# 1_Interface.net
KiCad netlist of a schematic drawn in Altium Designer
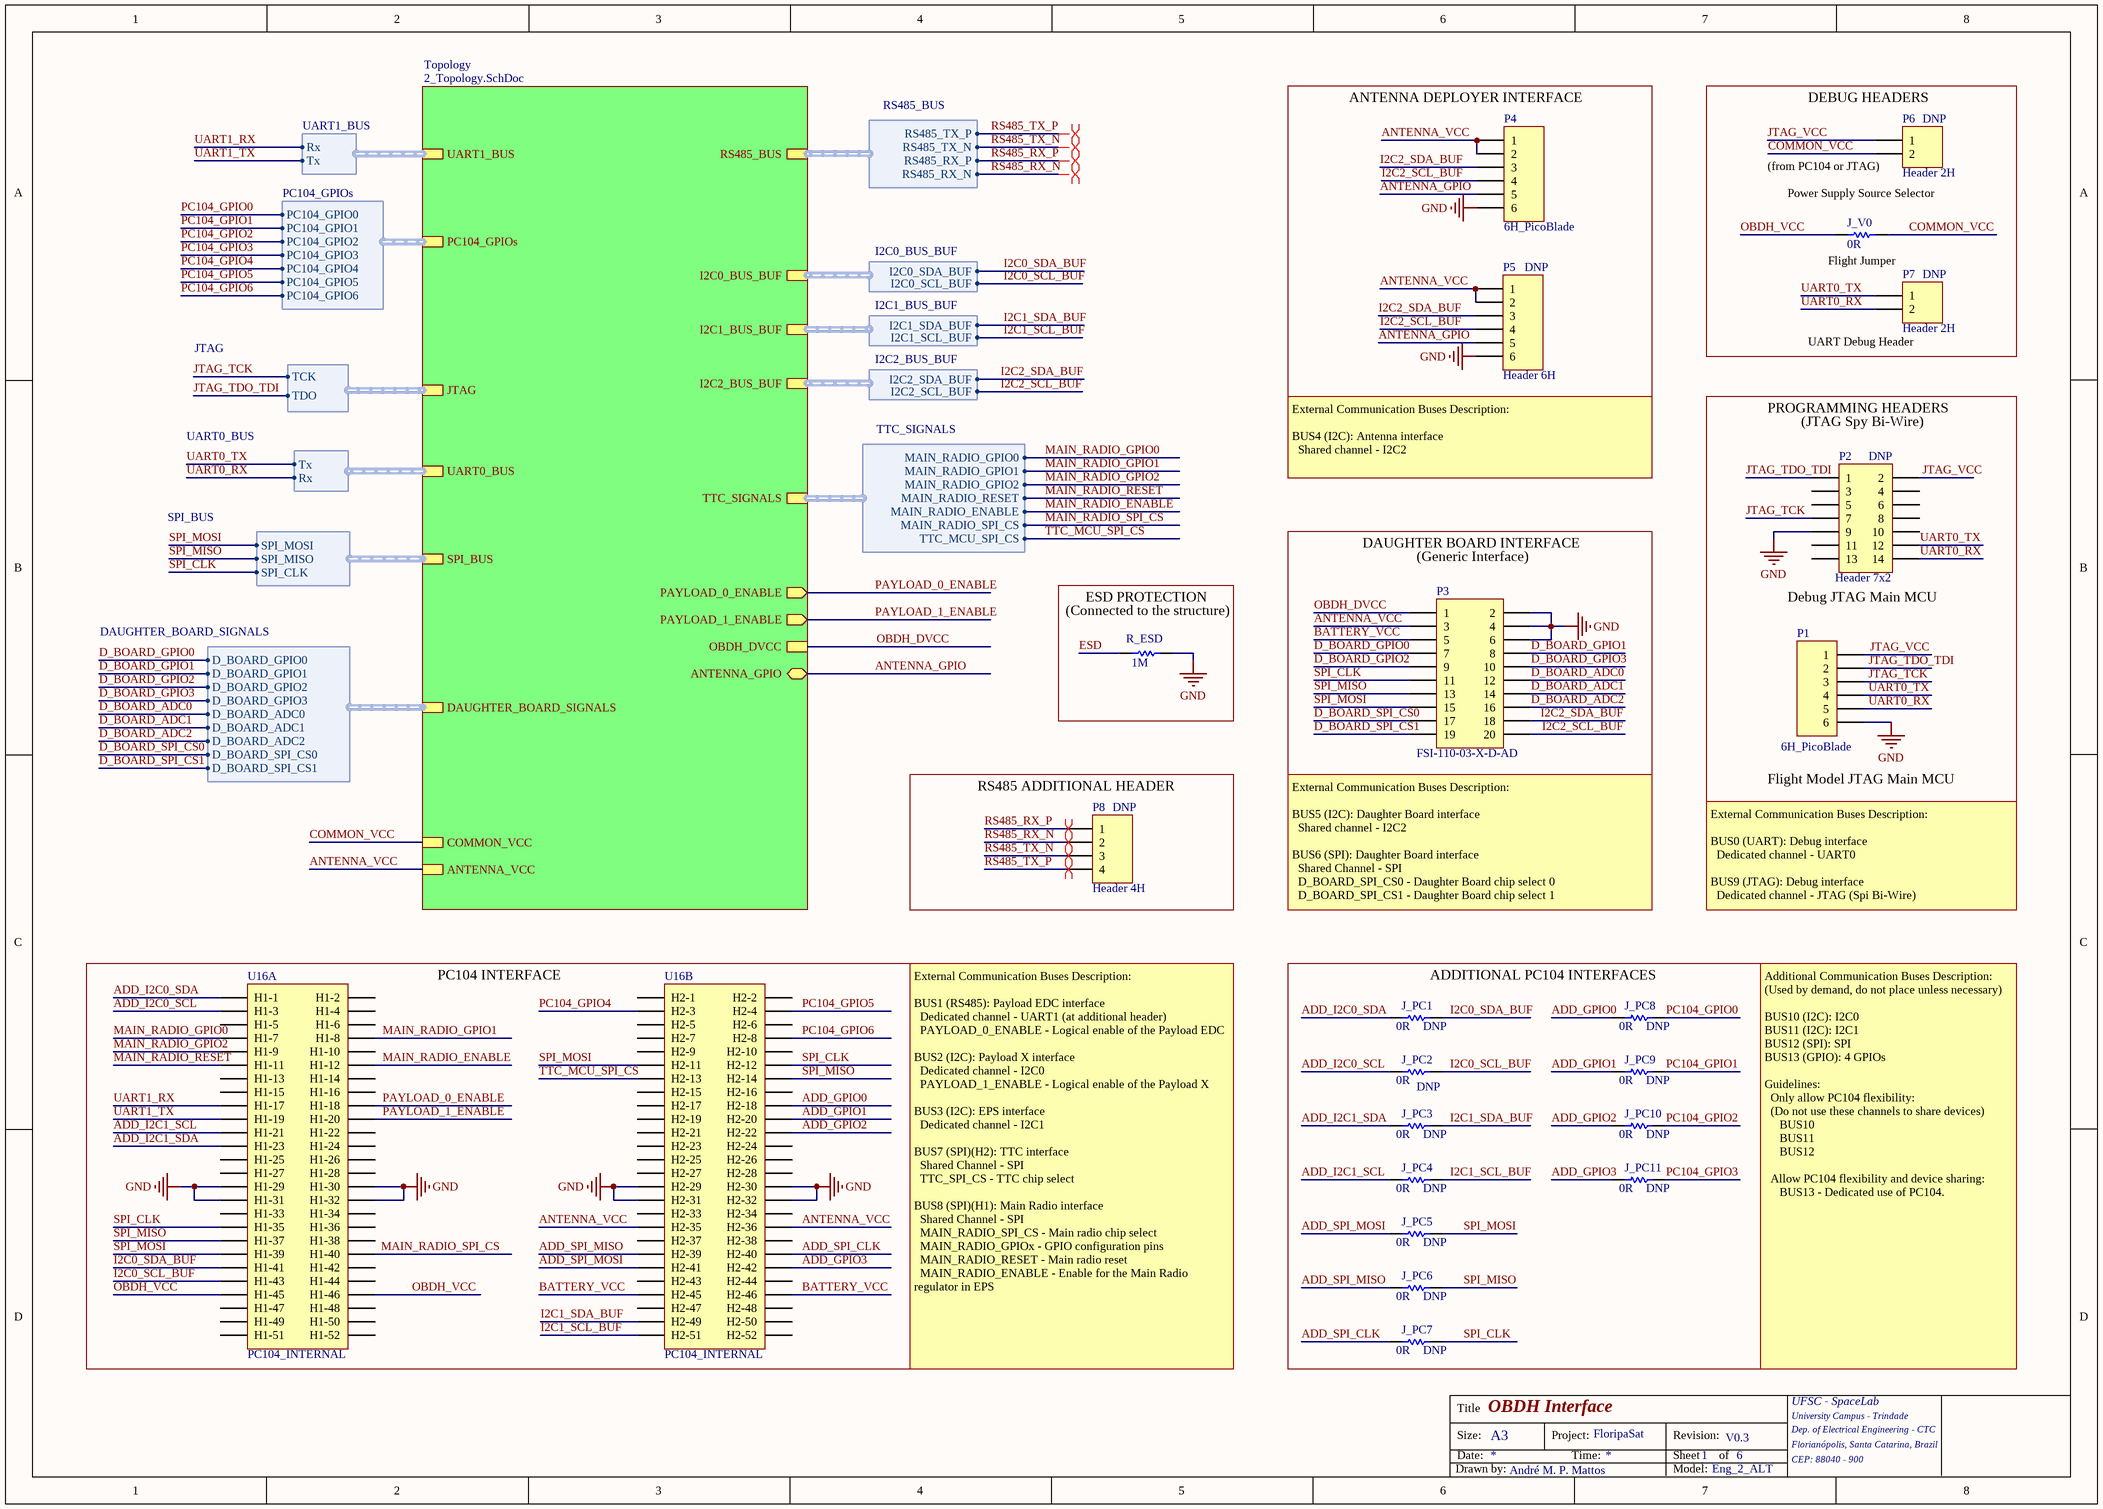
[diagram p0: 1_Interface.SchDoc]

(export (version "E")
  (design (tool "Eeschema 10.0.6"))
  (components
    (comp (ref "J_PC1")
      (value "0R")
      (footprint "0805")
      (description "RES 0R OHM 1/16W JUMPER 0805")
      (fields (field (name "PARTNUMBER") "CRCW08050000Z0EA"))
      (libsource (lib "OBDH_Eng_Model_2_ALT") (part "R0R_JUMPER_1/16W_0805"))
    )
    (comp (ref "J_PC2")
      (value "0R")
      (footprint "0805")
      (description "RES 0R OHM 1/16W JUMPER 0805")
      (fields (field (name "PARTNUMBER") "CRCW08050000Z0EA"))
      (libsource (lib "OBDH_Eng_Model_2_ALT") (part "R0R_JUMPER_1/16W_0805"))
    )
    (comp (ref "J_PC3")
      (value "0R")
      (footprint "0805")
      (description "RES 0R OHM 1/16W JUMPER 0805")
      (fields (field (name "PARTNUMBER") "CRCW08050000Z0EA"))
      (libsource (lib "OBDH_Eng_Model_2_ALT") (part "R0R_JUMPER_1/16W_0805"))
    )
    (comp (ref "J_PC4")
      (value "0R")
      (footprint "0805")
      (description "RES 0R OHM 1/16W JUMPER 0805")
      (fields (field (name "PARTNUMBER") "CRCW08050000Z0EA"))
      (libsource (lib "OBDH_Eng_Model_2_ALT") (part "R0R_JUMPER_1/16W_0805"))
    )
    (comp (ref "J_PC5")
      (value "0R")
      (footprint "0805")
      (description "RES 0R OHM 1/16W JUMPER 0805")
      (fields (field (name "PARTNUMBER") "CRCW08050000Z0EA"))
      (libsource (lib "OBDH_Eng_Model_2_ALT") (part "R0R_JUMPER_1/16W_0805"))
    )
    (comp (ref "J_PC6")
      (value "0R")
      (footprint "0805")
      (description "RES 0R OHM 1/16W JUMPER 0805")
      (fields (field (name "PARTNUMBER") "CRCW08050000Z0EA"))
      (libsource (lib "OBDH_Eng_Model_2_ALT") (part "R0R_JUMPER_1/16W_0805"))
    )
    (comp (ref "J_PC7")
      (value "0R")
      (footprint "0805")
      (description "RES 0R OHM 1/16W JUMPER 0805")
      (fields (field (name "PARTNUMBER") "CRCW08050000Z0EA"))
      (libsource (lib "OBDH_Eng_Model_2_ALT") (part "R0R_JUMPER_1/16W_0805"))
    )
    (comp (ref "J_PC8")
      (value "0R")
      (footprint "0805")
      (description "RES 0R OHM 1/16W JUMPER 0805")
      (fields (field (name "PARTNUMBER") "CRCW08050000Z0EA"))
      (libsource (lib "OBDH_Eng_Model_2_ALT") (part "R0R_JUMPER_1/16W_0805"))
    )
    (comp (ref "J_PC9")
      (value "0R")
      (footprint "0805")
      (description "RES 0R OHM 1/16W JUMPER 0805")
      (fields (field (name "PARTNUMBER") "CRCW08050000Z0EA"))
      (libsource (lib "OBDH_Eng_Model_2_ALT") (part "R0R_JUMPER_1/16W_0805"))
    )
    (comp (ref "J_PC10")
      (value "0R")
      (footprint "0805")
      (description "RES 0R OHM 1/16W JUMPER 0805")
      (fields (field (name "PARTNUMBER") "CRCW08050000Z0EA"))
      (libsource (lib "OBDH_Eng_Model_2_ALT") (part "R0R_JUMPER_1/16W_0805"))
    )
    (comp (ref "J_PC11")
      (value "0R")
      (footprint "0805")
      (description "RES 0R OHM 1/16W JUMPER 0805")
      (fields (field (name "PARTNUMBER") "CRCW08050000Z0EA"))
      (libsource (lib "OBDH_Eng_Model_2_ALT") (part "R0R_JUMPER_1/16W_0805"))
    )
    (comp (ref "J_V0")
      (value "0R")
      (footprint "0805")
      (description "RES 0R OHM 1/16W JUMPER 0805")
      (fields (field (name "PARTNUMBER") "CRCW08050000Z0EA"))
      (libsource (lib "OBDH_Eng_Model_2_ALT") (part "R0R_JUMPER_1/16W_0805"))
    )
    (comp (ref "P1")
      (value "6H_PicoBlade")
      (footprint "HDR6 PicoBlade")
      (description "Header, 6-Pin, Right Angle")
      (fields (field (name "PARTNUMBER") "53398-0671") (field (name "PUBLISHER") "Altium Limited"))
      (libsource (lib "OBDH_Eng_Model_2_ALT") (part "Header 6H_PicoBlade"))
    )
    (comp (ref "P2")
      (value "Header 7x2")
      (footprint "HDR2X7")
      (description "Header, 7-Pin, Dual row")
      (fields (field (name "PUBLISHER") "Altium Limited"))
      (libsource (lib "Miscellaneous Connectors") (part "Header 7X2"))
    )
    (comp (ref "P3")
      (value "FSI-110-03-X-D-AD")
      (footprint "FSI-110-03-X-D-AD")
      (description "Contact Connector")
      (fields (field (name "PARTNUMBER") "FSI-110-03-G-D-AD"))
      (libsource (lib "OBDH_Eng_Model_2_ALT") (part "FSI-110-03-X-D-AD"))
    )
    (comp (ref "P4")
      (value "6H_PicoBlade")
      (footprint "HDR6 PicoBlade")
      (description "Header, 6-Pin, Right Angle")
      (fields (field (name "PARTNUMBER") "53398-0671") (field (name "PUBLISHER") "Altium Limited"))
      (libsource (lib "") (part "Header 6H_PicoBlade_1"))
    )
    (comp (ref "P5")
      (value "Header 6H")
      (footprint "HDR1X6H")
      (description "Header, 6-Pin, Right Angle")
      (fields (field (name "PUBLISHER") "Altium Limited"))
      (libsource (lib "OBDH_Eng_Model_2_ALT") (part "Header 6H"))
    )
    (comp (ref "P6")
      (value "Header 2H")
      (footprint "HDR 1X2")
      (description "Header, 2-Pin")
      (fields (field (name "PARTNUMBER") "826646-2") (field (name "PUBLISHER") "Altium Limited"))
      (libsource (lib "OBDH_Eng_Model_2_ALT") (part "Header 2"))
    )
    (comp (ref "P7")
      (value "Header 2H")
      (footprint "HDR 1X2")
      (description "Header, 2-Pin")
      (fields (field (name "PARTNUMBER") "826646-2") (field (name "PUBLISHER") "Altium Limited"))
      (libsource (lib "OBDH_Eng_Model_2_ALT") (part "Header 2"))
    )
    (comp (ref "P8")
      (value "Header 4H")
      (footprint "HDR1X4")
      (description "Header, 4-Pin")
      (fields (field (name "PUBLISHER") "Altium Limited"))
      (libsource (lib "OBDH_Eng_Model_2_ALT") (part "Header 4H"))
    )
    (comp (ref "R_ESD")
      (value "1M")
      (footprint "0805")
      (description "RES 1000K OHM 1/8W 1% 0805")
      (fields (field (name "PARTNUMBER") "AC0805FR-13100KL"))
      (libsource (lib "OBDH_Eng_Model_2_ALT") (part "R1000k_1%_1/8W_0805"))
    )
    (comp (ref "U16")
      (value "PC104_INTERNAL")
      (footprint "PC104")
      (description "PC104")
      (fields (field (name "PARTNUMBER") "SSW-126-04-G-D"))
      (libsource (lib "OBDH_Eng_Model_2_ALT") (part "PC104"))
    )
  )
  (nets
    (net (code "13") (name "/ADD_GPIO0") (class "Default")
      (node (ref "J_PC8") (pin "1") (pinfunction "1_1") (pintype "passive"))
      (node (ref "U16") (pin "H2-18") (pinfunction "H2-18_H2-18") (pintype "passive"))
    )
    (net (code "14") (name "/ADD_GPIO1") (class "Default")
      (node (ref "J_PC9") (pin "1") (pinfunction "1_1") (pintype "passive"))
      (node (ref "U16") (pin "H2-20") (pinfunction "H2-20_H2-20") (pintype "passive"))
    )
    (net (code "15") (name "/ADD_GPIO2") (class "Default")
      (node (ref "J_PC10") (pin "1") (pinfunction "1_1") (pintype "passive"))
      (node (ref "U16") (pin "H2-22") (pinfunction "H2-22_H2-22") (pintype "passive"))
    )
    (net (code "16") (name "/ADD_GPIO3") (class "Default")
      (node (ref "J_PC11") (pin "1") (pinfunction "1_1") (pintype "passive"))
      (node (ref "U16") (pin "H2-42") (pinfunction "H2-42_H2-42") (pintype "passive"))
    )
    (net (code "17") (name "/ADD_I2C0_SCL") (class "Default")
      (node (ref "J_PC2") (pin "1") (pinfunction "1_1") (pintype "passive"))
      (node (ref "U16") (pin "H1-3") (pinfunction "H1-3_H1-3") (pintype "passive"))
    )
    (net (code "18") (name "/ADD_I2C0_SDA") (class "Default")
      (node (ref "J_PC1") (pin "1") (pinfunction "1_1") (pintype "passive"))
      (node (ref "U16") (pin "H1-1") (pinfunction "H1-1_H1-1") (pintype "passive"))
    )
    (net (code "19") (name "/ADD_I2C1_SCL") (class "Default")
      (node (ref "J_PC4") (pin "1") (pinfunction "1_1") (pintype "passive"))
      (node (ref "U16") (pin "H1-21") (pinfunction "H1-21_H1-21") (pintype "passive"))
    )
    (net (code "20") (name "/ADD_I2C1_SDA") (class "Default")
      (node (ref "J_PC3") (pin "1") (pinfunction "1_1") (pintype "passive"))
      (node (ref "U16") (pin "H1-23") (pinfunction "H1-23_H1-23") (pintype "passive"))
    )
    (net (code "21") (name "/ADD_SPI_CLK") (class "Default")
      (node (ref "J_PC7") (pin "1") (pinfunction "1_1") (pintype "passive"))
      (node (ref "U16") (pin "H2-40") (pinfunction "H2-40_H2-40") (pintype "passive"))
    )
    (net (code "22") (name "/ADD_SPI_MISO") (class "Default")
      (node (ref "J_PC6") (pin "1") (pinfunction "1_1") (pintype "passive"))
      (node (ref "U16") (pin "H2-39") (pinfunction "H2-39_H2-39") (pintype "passive"))
    )
    (net (code "23") (name "/ADD_SPI_MOSI") (class "Default")
      (node (ref "J_PC5") (pin "1") (pinfunction "1_1") (pintype "passive"))
      (node (ref "U16") (pin "H2-41") (pinfunction "H2-41_H2-41") (pintype "passive"))
    )
    (net (code "24") (name "/ANTENNA_GPIO") (class "Default")
      (node (ref "P4") (pin "5") (pinfunction "5_5") (pintype "passive"))
      (node (ref "P5") (pin "5") (pinfunction "5_5") (pintype "passive"))
    )
    (net (code "25") (name "/ANTENNA_VCC") (class "Default")
      (node (ref "P3") (pin "3") (pinfunction "3_3") (pintype "passive"))
      (node (ref "P4") (pin "1") (pinfunction "1_1") (pintype "passive"))
      (node (ref "P4") (pin "2") (pinfunction "2_2") (pintype "passive"))
      (node (ref "P5") (pin "1") (pinfunction "1_1") (pintype "passive"))
      (node (ref "P5") (pin "2") (pinfunction "2_2") (pintype "passive"))
      (node (ref "U16") (pin "H2-35") (pinfunction "H2-35_H2-35") (pintype "passive"))
      (node (ref "U16") (pin "H2-36") (pinfunction "H2-36_H2-36") (pintype "passive"))
    )
    (net (code "26") (name "/BATTERY_VCC") (class "Default")
      (node (ref "P3") (pin "5") (pinfunction "5_5") (pintype "passive"))
      (node (ref "U16") (pin "H2-45") (pinfunction "H2-45_H2-45") (pintype "passive"))
      (node (ref "U16") (pin "H2-46") (pinfunction "H2-46_H2-46") (pintype "passive"))
    )
    (net (code "27") (name "/COMMON_VCC") (class "Default")
      (node (ref "J_V0") (pin "2") (pinfunction "2_2") (pintype "passive"))
      (node (ref "P6") (pin "2") (pinfunction "2_2") (pintype "passive"))
    )
    (net (code "28") (name "/D_BOARD_ADC0") (class "Default")
      (node (ref "P3") (pin "12") (pinfunction "12_12") (pintype "passive"))
    )
    (net (code "29") (name "/D_BOARD_ADC1") (class "Default")
      (node (ref "P3") (pin "14") (pinfunction "14_14") (pintype "passive"))
    )
    (net (code "30") (name "/D_BOARD_ADC2") (class "Default")
      (node (ref "P3") (pin "16") (pinfunction "16_16") (pintype "passive"))
    )
    (net (code "31") (name "/D_BOARD_GPIO0") (class "Default")
      (node (ref "P3") (pin "7") (pinfunction "7_7") (pintype "passive"))
    )
    (net (code "32") (name "/D_BOARD_GPIO1") (class "Default")
      (node (ref "P3") (pin "8") (pinfunction "8_8") (pintype "passive"))
    )
    (net (code "33") (name "/D_BOARD_GPIO2") (class "Default")
      (node (ref "P3") (pin "9") (pinfunction "9_9") (pintype "passive"))
    )
    (net (code "34") (name "/D_BOARD_GPIO3") (class "Default")
      (node (ref "P3") (pin "10") (pinfunction "10_10") (pintype "passive"))
    )
    (net (code "35") (name "/D_BOARD_SPI_CS0") (class "Default")
      (node (ref "P3") (pin "17") (pinfunction "17_17") (pintype "passive"))
    )
    (net (code "36") (name "/D_BOARD_SPI_CS1") (class "Default")
      (node (ref "P3") (pin "19") (pinfunction "19_19") (pintype "passive"))
    )
    (net (code "37") (name "/ESD") (class "Default")
      (node (ref "R_ESD") (pin "2") (pinfunction "2_2") (pintype "passive"))
    )
    (net (code "38") (name "/I2C0_SCL_BUF") (class "Default")
      (node (ref "J_PC2") (pin "2") (pinfunction "2_2") (pintype "passive"))
      (node (ref "U16") (pin "H1-43") (pinfunction "H1-43_H1-43") (pintype "passive"))
    )
    (net (code "39") (name "/I2C0_SDA_BUF") (class "Default")
      (node (ref "J_PC1") (pin "2") (pinfunction "2_2") (pintype "passive"))
      (node (ref "U16") (pin "H1-41") (pinfunction "H1-41_H1-41") (pintype "passive"))
    )
    (net (code "40") (name "/I2C1_SCL_BUF") (class "Default")
      (node (ref "J_PC4") (pin "2") (pinfunction "2_2") (pintype "passive"))
      (node (ref "U16") (pin "H2-51") (pinfunction "H2-51_H2-51") (pintype "passive"))
    )
    (net (code "41") (name "/I2C1_SDA_BUF") (class "Default")
      (node (ref "J_PC3") (pin "2") (pinfunction "2_2") (pintype "passive"))
      (node (ref "U16") (pin "H2-49") (pinfunction "H2-49_H2-49") (pintype "passive"))
    )
    (net (code "42") (name "/I2C2_SCL_BUF") (class "Default")
      (node (ref "P3") (pin "20") (pinfunction "20_20") (pintype "passive"))
      (node (ref "P4") (pin "4") (pinfunction "4_4") (pintype "passive"))
      (node (ref "P5") (pin "4") (pinfunction "4_4") (pintype "passive"))
    )
    (net (code "43") (name "/I2C2_SDA_BUF") (class "Default")
      (node (ref "P3") (pin "18") (pinfunction "18_18") (pintype "passive"))
      (node (ref "P4") (pin "3") (pinfunction "3_3") (pintype "passive"))
      (node (ref "P5") (pin "3") (pinfunction "3_3") (pintype "passive"))
    )
    (net (code "44") (name "/JTAG_TCK") (class "Default")
      (node (ref "P1") (pin "3") (pinfunction "3_3") (pintype "passive"))
      (node (ref "P2") (pin "7") (pinfunction "7_7") (pintype "passive"))
    )
    (net (code "45") (name "/JTAG_TDO_TDI") (class "Default")
      (node (ref "P1") (pin "2") (pinfunction "2_2") (pintype "passive"))
      (node (ref "P2") (pin "1") (pinfunction "1_1") (pintype "passive"))
    )
    (net (code "46") (name "/JTAG_VCC") (class "Default")
      (node (ref "P1") (pin "1") (pinfunction "1_1") (pintype "passive"))
      (node (ref "P2") (pin "2") (pinfunction "2_2") (pintype "passive"))
      (node (ref "P6") (pin "1") (pinfunction "1_1") (pintype "passive"))
    )
    (net (code "47") (name "/MAIN_RADIO_ENABLE") (class "Default")
      (node (ref "U16") (pin "H1-12") (pinfunction "H1-12_H1-12") (pintype "passive"))
    )
    (net (code "48") (name "/MAIN_RADIO_GPIO0") (class "Default")
      (node (ref "U16") (pin "H1-7") (pinfunction "H1-7_H1-7") (pintype "passive"))
    )
    (net (code "49") (name "/MAIN_RADIO_GPIO1") (class "Default")
      (node (ref "U16") (pin "H1-8") (pinfunction "H1-8_H1-8") (pintype "passive"))
    )
    (net (code "50") (name "/MAIN_RADIO_GPIO2") (class "Default")
      (node (ref "U16") (pin "H1-9") (pinfunction "H1-9_H1-9") (pintype "passive"))
    )
    (net (code "51") (name "/MAIN_RADIO_RESET") (class "Default")
      (node (ref "U16") (pin "H1-11") (pinfunction "H1-11_H1-11") (pintype "passive"))
    )
    (net (code "52") (name "/MAIN_RADIO_SPI_CS") (class "Default")
      (node (ref "U16") (pin "H1-40") (pinfunction "H1-40_H1-40") (pintype "passive"))
    )
    (net (code "53") (name "/OBDH_DVCC") (class "Default")
      (node (ref "P3") (pin "1") (pinfunction "1_1") (pintype "passive"))
    )
    (net (code "54") (name "/OBDH_VCC") (class "Default")
      (node (ref "J_V0") (pin "1") (pinfunction "1_1") (pintype "passive"))
      (node (ref "U16") (pin "H1-45") (pinfunction "H1-45_H1-45") (pintype "passive"))
      (node (ref "U16") (pin "H1-46") (pinfunction "H1-46_H1-46") (pintype "passive"))
    )
    (net (code "55") (name "/PAYLOAD_0_ENABLE") (class "Default")
      (node (ref "U16") (pin "H1-18") (pinfunction "H1-18_H1-18") (pintype "passive"))
    )
    (net (code "56") (name "/PAYLOAD_1_ENABLE") (class "Default")
      (node (ref "U16") (pin "H1-20") (pinfunction "H1-20_H1-20") (pintype "passive"))
    )
    (net (code "57") (name "/PC104_GPIO0") (class "Default")
      (node (ref "J_PC8") (pin "2") (pinfunction "2_2") (pintype "passive"))
    )
    (net (code "58") (name "/PC104_GPIO1") (class "Default")
      (node (ref "J_PC9") (pin "2") (pinfunction "2_2") (pintype "passive"))
    )
    (net (code "59") (name "/PC104_GPIO2") (class "Default")
      (node (ref "J_PC10") (pin "2") (pinfunction "2_2") (pintype "passive"))
    )
    (net (code "60") (name "/PC104_GPIO3") (class "Default")
      (node (ref "J_PC11") (pin "2") (pinfunction "2_2") (pintype "passive"))
    )
    (net (code "61") (name "/PC104_GPIO4") (class "Default")
      (node (ref "U16") (pin "H2-3") (pinfunction "H2-3_H2-3") (pintype "passive"))
    )
    (net (code "62") (name "/PC104_GPIO5") (class "Default")
      (node (ref "U16") (pin "H2-4") (pinfunction "H2-4_H2-4") (pintype "passive"))
    )
    (net (code "63") (name "/PC104_GPIO6") (class "Default")
      (node (ref "U16") (pin "H2-8") (pinfunction "H2-8_H2-8") (pintype "passive"))
    )
    (net (code "64") (name "/RS485_RX_N") (class "Default")
      (node (ref "P8") (pin "2") (pinfunction "2_2") (pintype "passive"))
    )
    (net (code "65") (name "/RS485_RX_P") (class "Default")
      (node (ref "P8") (pin "1") (pinfunction "1_1") (pintype "passive"))
    )
    (net (code "66") (name "/RS485_TX_N") (class "Default")
      (node (ref "P8") (pin "3") (pinfunction "3_3") (pintype "passive"))
    )
    (net (code "67") (name "/RS485_TX_P") (class "Default")
      (node (ref "P8") (pin "4") (pinfunction "4_4") (pintype "passive"))
    )
    (net (code "68") (name "/SPI_CLK") (class "Default")
      (node (ref "J_PC7") (pin "2") (pinfunction "2_2") (pintype "passive"))
      (node (ref "P3") (pin "11") (pinfunction "11_11") (pintype "passive"))
      (node (ref "U16") (pin "H1-35") (pinfunction "H1-35_H1-35") (pintype "passive"))
      (node (ref "U16") (pin "H2-12") (pinfunction "H2-12_H2-12") (pintype "passive"))
    )
    (net (code "69") (name "/SPI_MISO") (class "Default")
      (node (ref "J_PC6") (pin "2") (pinfunction "2_2") (pintype "passive"))
      (node (ref "P3") (pin "13") (pinfunction "13_13") (pintype "passive"))
      (node (ref "U16") (pin "H1-37") (pinfunction "H1-37_H1-37") (pintype "passive"))
      (node (ref "U16") (pin "H2-14") (pinfunction "H2-14_H2-14") (pintype "passive"))
    )
    (net (code "70") (name "/SPI_MOSI") (class "Default")
      (node (ref "J_PC5") (pin "2") (pinfunction "2_2") (pintype "passive"))
      (node (ref "P3") (pin "15") (pinfunction "15_15") (pintype "passive"))
      (node (ref "U16") (pin "H1-39") (pinfunction "H1-39_H1-39") (pintype "passive"))
      (node (ref "U16") (pin "H2-11") (pinfunction "H2-11_H2-11") (pintype "passive"))
    )
    (net (code "71") (name "/TTC_MCU_SPI_CS") (class "Default")
      (node (ref "U16") (pin "H2-13") (pinfunction "H2-13_H2-13") (pintype "passive"))
    )
    (net (code "72") (name "/UART0_RX") (class "Default")
      (node (ref "P1") (pin "5") (pinfunction "5_5") (pintype "passive"))
      (node (ref "P2") (pin "14") (pinfunction "14_14") (pintype "passive"))
      (node (ref "P7") (pin "2") (pinfunction "2_2") (pintype "passive"))
    )
    (net (code "73") (name "/UART0_TX") (class "Default")
      (node (ref "P1") (pin "4") (pinfunction "4_4") (pintype "passive"))
      (node (ref "P2") (pin "12") (pinfunction "12_12") (pintype "passive"))
      (node (ref "P7") (pin "1") (pinfunction "1_1") (pintype "passive"))
    )
    (net (code "74") (name "/UART1_RX") (class "Default")
      (node (ref "U16") (pin "H1-17") (pinfunction "H1-17_H1-17") (pintype "passive"))
    )
    (net (code "75") (name "/UART1_TX") (class "Default")
      (node (ref "U16") (pin "H1-19") (pinfunction "H1-19_H1-19") (pintype "passive"))
    )
    (net (code "87") (name "GND") (class "Default")
      (node (ref "P1") (pin "6") (pinfunction "6_6") (pintype "passive"))
      (node (ref "P2") (pin "9") (pinfunction "9_9") (pintype "passive"))
      (node (ref "P3") (pin "2") (pinfunction "2_2") (pintype "passive"))
      (node (ref "P3") (pin "4") (pinfunction "4_4") (pintype "passive"))
      (node (ref "P3") (pin "6") (pinfunction "6_6") (pintype "passive"))
      (node (ref "P4") (pin "6") (pinfunction "6_6") (pintype "passive"))
      (node (ref "P5") (pin "6") (pinfunction "6_6") (pintype "passive"))
      (node (ref "R_ESD") (pin "1") (pinfunction "1_1") (pintype "passive"))
      (node (ref "U16") (pin "H1-29") (pinfunction "H1-29_H1-29") (pintype "passive"))
      (node (ref "U16") (pin "H1-30") (pinfunction "H1-30_H1-30") (pintype "passive"))
      (node (ref "U16") (pin "H1-31") (pinfunction "H1-31_H1-31") (pintype "passive"))
      (node (ref "U16") (pin "H1-32") (pinfunction "H1-32_H1-32") (pintype "passive"))
      (node (ref "U16") (pin "H2-29") (pinfunction "H2-29_H2-29") (pintype "passive"))
      (node (ref "U16") (pin "H2-30") (pinfunction "H2-30_H2-30") (pintype "passive"))
      (node (ref "U16") (pin "H2-31") (pinfunction "H2-31_H2-31") (pintype "passive"))
      (node (ref "U16") (pin "H2-32") (pinfunction "H2-32_H2-32") (pintype "passive"))
    )
    (net (code "88") (name "unconnected-(P2-Pad3)") (class "Default")
      (node (ref "P2") (pin "3") (pinfunction "3_3") (pintype "passive"))
    )
    (net (code "89") (name "unconnected-(P2-Pad4)") (class "Default")
      (node (ref "P2") (pin "4") (pinfunction "4_4") (pintype "passive"))
    )
    (net (code "90") (name "unconnected-(P2-Pad5)") (class "Default")
      (node (ref "P2") (pin "5") (pinfunction "5_5") (pintype "passive"))
    )
    (net (code "91") (name "unconnected-(P2-Pad6)") (class "Default")
      (node (ref "P2") (pin "6") (pinfunction "6_6") (pintype "passive"))
    )
    (net (code "92") (name "unconnected-(P2-Pad8)") (class "Default")
      (node (ref "P2") (pin "8") (pinfunction "8_8") (pintype "passive"))
    )
    (net (code "93") (name "unconnected-(P2-Pad10)") (class "Default")
      (node (ref "P2") (pin "10") (pinfunction "10_10") (pintype "passive"))
    )
    (net (code "94") (name "unconnected-(P2-Pad11)") (class "Default")
      (node (ref "P2") (pin "11") (pinfunction "11_11") (pintype "passive"))
    )
    (net (code "95") (name "unconnected-(P2-Pad13)") (class "Default")
      (node (ref "P2") (pin "13") (pinfunction "13_13") (pintype "passive"))
    )
    (net (code "96") (name "unconnected-(U16-PadH1-2)") (class "Default")
      (node (ref "U16") (pin "H1-2") (pinfunction "H1-2_H1-2") (pintype "passive"))
    )
    (net (code "97") (name "unconnected-(U16-PadH1-4)") (class "Default")
      (node (ref "U16") (pin "H1-4") (pinfunction "H1-4_H1-4") (pintype "passive"))
    )
    (net (code "98") (name "unconnected-(U16-PadH1-5)") (class "Default")
      (node (ref "U16") (pin "H1-5") (pinfunction "H1-5_H1-5") (pintype "passive"))
    )
    (net (code "99") (name "unconnected-(U16-PadH1-6)") (class "Default")
      (node (ref "U16") (pin "H1-6") (pinfunction "H1-6_H1-6") (pintype "passive"))
    )
    (net (code "100") (name "unconnected-(U16-PadH1-10)") (class "Default")
      (node (ref "U16") (pin "H1-10") (pinfunction "H1-10_H1-10") (pintype "passive"))
    )
    (net (code "101") (name "unconnected-(U16-PadH1-13)") (class "Default")
      (node (ref "U16") (pin "H1-13") (pinfunction "H1-13_H1-13") (pintype "passive"))
    )
    (net (code "102") (name "unconnected-(U16-PadH1-14)") (class "Default")
      (node (ref "U16") (pin "H1-14") (pinfunction "H1-14_H1-14") (pintype "passive"))
    )
    (net (code "103") (name "unconnected-(U16-PadH1-15)") (class "Default")
      (node (ref "U16") (pin "H1-15") (pinfunction "H1-15_H1-15") (pintype "passive"))
    )
    (net (code "104") (name "unconnected-(U16-PadH1-16)") (class "Default")
      (node (ref "U16") (pin "H1-16") (pinfunction "H1-16_H1-16") (pintype "passive"))
    )
    (net (code "105") (name "unconnected-(U16-PadH1-22)") (class "Default")
      (node (ref "U16") (pin "H1-22") (pinfunction "H1-22_H1-22") (pintype "passive"))
    )
    (net (code "106") (name "unconnected-(U16-PadH1-24)") (class "Default")
      (node (ref "U16") (pin "H1-24") (pinfunction "H1-24_H1-24") (pintype "passive"))
    )
    (net (code "107") (name "unconnected-(U16-PadH1-25)") (class "Default")
      (node (ref "U16") (pin "H1-25") (pinfunction "H1-25_H1-25") (pintype "passive"))
    )
    (net (code "108") (name "unconnected-(U16-PadH1-26)") (class "Default")
      (node (ref "U16") (pin "H1-26") (pinfunction "H1-26_H1-26") (pintype "passive"))
    )
    (net (code "109") (name "unconnected-(U16-PadH1-27)") (class "Default")
      (node (ref "U16") (pin "H1-27") (pinfunction "H1-27_H1-27") (pintype "passive"))
    )
    (net (code "110") (name "unconnected-(U16-PadH1-28)") (class "Default")
      (node (ref "U16") (pin "H1-28") (pinfunction "H1-28_H1-28") (pintype "passive"))
    )
    (net (code "111") (name "unconnected-(U16-PadH1-33)") (class "Default")
      (node (ref "U16") (pin "H1-33") (pinfunction "H1-33_H1-33") (pintype "passive"))
    )
    (net (code "112") (name "unconnected-(U16-PadH1-34)") (class "Default")
      (node (ref "U16") (pin "H1-34") (pinfunction "H1-34_H1-34") (pintype "passive"))
    )
    (net (code "113") (name "unconnected-(U16-PadH1-36)") (class "Default")
      (node (ref "U16") (pin "H1-36") (pinfunction "H1-36_H1-36") (pintype "passive"))
    )
    (net (code "114") (name "unconnected-(U16-PadH1-38)") (class "Default")
      (node (ref "U16") (pin "H1-38") (pinfunction "H1-38_H1-38") (pintype "passive"))
    )
    (net (code "115") (name "unconnected-(U16-PadH1-42)") (class "Default")
      (node (ref "U16") (pin "H1-42") (pinfunction "H1-42_H1-42") (pintype "passive"))
    )
    (net (code "116") (name "unconnected-(U16-PadH1-44)") (class "Default")
      (node (ref "U16") (pin "H1-44") (pinfunction "H1-44_H1-44") (pintype "passive"))
    )
    (net (code "117") (name "unconnected-(U16-PadH1-47)") (class "Default")
      (node (ref "U16") (pin "H1-47") (pinfunction "H1-47_H1-47") (pintype "passive"))
    )
    (net (code "118") (name "unconnected-(U16-PadH1-48)") (class "Default")
      (node (ref "U16") (pin "H1-48") (pinfunction "H1-48_H1-48") (pintype "passive"))
    )
    (net (code "119") (name "unconnected-(U16-PadH1-49)") (class "Default")
      (node (ref "U16") (pin "H1-49") (pinfunction "H1-49_H1-49") (pintype "passive"))
    )
    (net (code "120") (name "unconnected-(U16-PadH1-50)") (class "Default")
      (node (ref "U16") (pin "H1-50") (pinfunction "H1-50_H1-50") (pintype "passive"))
    )
    (net (code "121") (name "unconnected-(U16-PadH1-51)") (class "Default")
      (node (ref "U16") (pin "H1-51") (pinfunction "H1-51_H1-51") (pintype "passive"))
    )
    (net (code "122") (name "unconnected-(U16-PadH1-52)") (class "Default")
      (node (ref "U16") (pin "H1-52") (pinfunction "H1-52_H1-52") (pintype "passive"))
    )
    (net (code "123") (name "unconnected-(U16-PadH2-1)") (class "Default")
      (node (ref "U16") (pin "H2-1") (pinfunction "H2-1_H2-1") (pintype "passive"))
    )
    (net (code "124") (name "unconnected-(U16-PadH2-2)") (class "Default")
      (node (ref "U16") (pin "H2-2") (pinfunction "H2-2_H2-2") (pintype "passive"))
    )
    (net (code "125") (name "unconnected-(U16-PadH2-5)") (class "Default")
      (node (ref "U16") (pin "H2-5") (pinfunction "H2-5_H2-5") (pintype "passive"))
    )
    (net (code "126") (name "unconnected-(U16-PadH2-6)") (class "Default")
      (node (ref "U16") (pin "H2-6") (pinfunction "H2-6_H2-6") (pintype "passive"))
    )
    (net (code "127") (name "unconnected-(U16-PadH2-7)") (class "Default")
      (node (ref "U16") (pin "H2-7") (pinfunction "H2-7_H2-7") (pintype "passive"))
    )
    (net (code "128") (name "unconnected-(U16-PadH2-9)") (class "Default")
      (node (ref "U16") (pin "H2-9") (pinfunction "H2-9_H2-9") (pintype "passive"))
    )
    (net (code "129") (name "unconnected-(U16-PadH2-10)") (class "Default")
      (node (ref "U16") (pin "H2-10") (pinfunction "H2-10_H2-10") (pintype "passive"))
    )
    (net (code "130") (name "unconnected-(U16-PadH2-15)") (class "Default")
      (node (ref "U16") (pin "H2-15") (pinfunction "H2-15_H2-15") (pintype "passive"))
    )
    (net (code "131") (name "unconnected-(U16-PadH2-16)") (class "Default")
      (node (ref "U16") (pin "H2-16") (pinfunction "H2-16_H2-16") (pintype "passive"))
    )
    (net (code "132") (name "unconnected-(U16-PadH2-17)") (class "Default")
      (node (ref "U16") (pin "H2-17") (pinfunction "H2-17_H2-17") (pintype "passive"))
    )
    (net (code "133") (name "unconnected-(U16-PadH2-19)") (class "Default")
      (node (ref "U16") (pin "H2-19") (pinfunction "H2-19_H2-19") (pintype "passive"))
    )
    (net (code "134") (name "unconnected-(U16-PadH2-21)") (class "Default")
      (node (ref "U16") (pin "H2-21") (pinfunction "H2-21_H2-21") (pintype "passive"))
    )
    (net (code "135") (name "unconnected-(U16-PadH2-23)") (class "Default")
      (node (ref "U16") (pin "H2-23") (pinfunction "H2-23_H2-23") (pintype "passive"))
    )
    (net (code "136") (name "unconnected-(U16-PadH2-24)") (class "Default")
      (node (ref "U16") (pin "H2-24") (pinfunction "H2-24_H2-24") (pintype "passive"))
    )
    (net (code "137") (name "unconnected-(U16-PadH2-25)") (class "Default")
      (node (ref "U16") (pin "H2-25") (pinfunction "H2-25_H2-25") (pintype "passive"))
    )
    (net (code "138") (name "unconnected-(U16-PadH2-26)") (class "Default")
      (node (ref "U16") (pin "H2-26") (pinfunction "H2-26_H2-26") (pintype "passive"))
    )
    (net (code "139") (name "unconnected-(U16-PadH2-27)") (class "Default")
      (node (ref "U16") (pin "H2-27") (pinfunction "H2-27_H2-27") (pintype "passive"))
    )
    (net (code "140") (name "unconnected-(U16-PadH2-28)") (class "Default")
      (node (ref "U16") (pin "H2-28") (pinfunction "H2-28_H2-28") (pintype "passive"))
    )
    (net (code "141") (name "unconnected-(U16-PadH2-33)") (class "Default")
      (node (ref "U16") (pin "H2-33") (pinfunction "H2-33_H2-33") (pintype "passive"))
    )
    (net (code "142") (name "unconnected-(U16-PadH2-34)") (class "Default")
      (node (ref "U16") (pin "H2-34") (pinfunction "H2-34_H2-34") (pintype "passive"))
    )
    (net (code "143") (name "unconnected-(U16-PadH2-37)") (class "Default")
      (node (ref "U16") (pin "H2-37") (pinfunction "H2-37_H2-37") (pintype "passive"))
    )
    (net (code "144") (name "unconnected-(U16-PadH2-38)") (class "Default")
      (node (ref "U16") (pin "H2-38") (pinfunction "H2-38_H2-38") (pintype "passive"))
    )
    (net (code "145") (name "unconnected-(U16-PadH2-43)") (class "Default")
      (node (ref "U16") (pin "H2-43") (pinfunction "H2-43_H2-43") (pintype "passive"))
    )
    (net (code "146") (name "unconnected-(U16-PadH2-44)") (class "Default")
      (node (ref "U16") (pin "H2-44") (pinfunction "H2-44_H2-44") (pintype "passive"))
    )
    (net (code "147") (name "unconnected-(U16-PadH2-47)") (class "Default")
      (node (ref "U16") (pin "H2-47") (pinfunction "H2-47_H2-47") (pintype "passive"))
    )
    (net (code "148") (name "unconnected-(U16-PadH2-48)") (class "Default")
      (node (ref "U16") (pin "H2-48") (pinfunction "H2-48_H2-48") (pintype "passive"))
    )
    (net (code "149") (name "unconnected-(U16-PadH2-50)") (class "Default")
      (node (ref "U16") (pin "H2-50") (pinfunction "H2-50_H2-50") (pintype "passive"))
    )
    (net (code "150") (name "unconnected-(U16-PadH2-52)") (class "Default")
      (node (ref "U16") (pin "H2-52") (pinfunction "H2-52_H2-52") (pintype "passive"))
    )
  )
)
